# DAUGHTERBOARD.net
KiCad netlist of a schematic drawn in Altium Designer
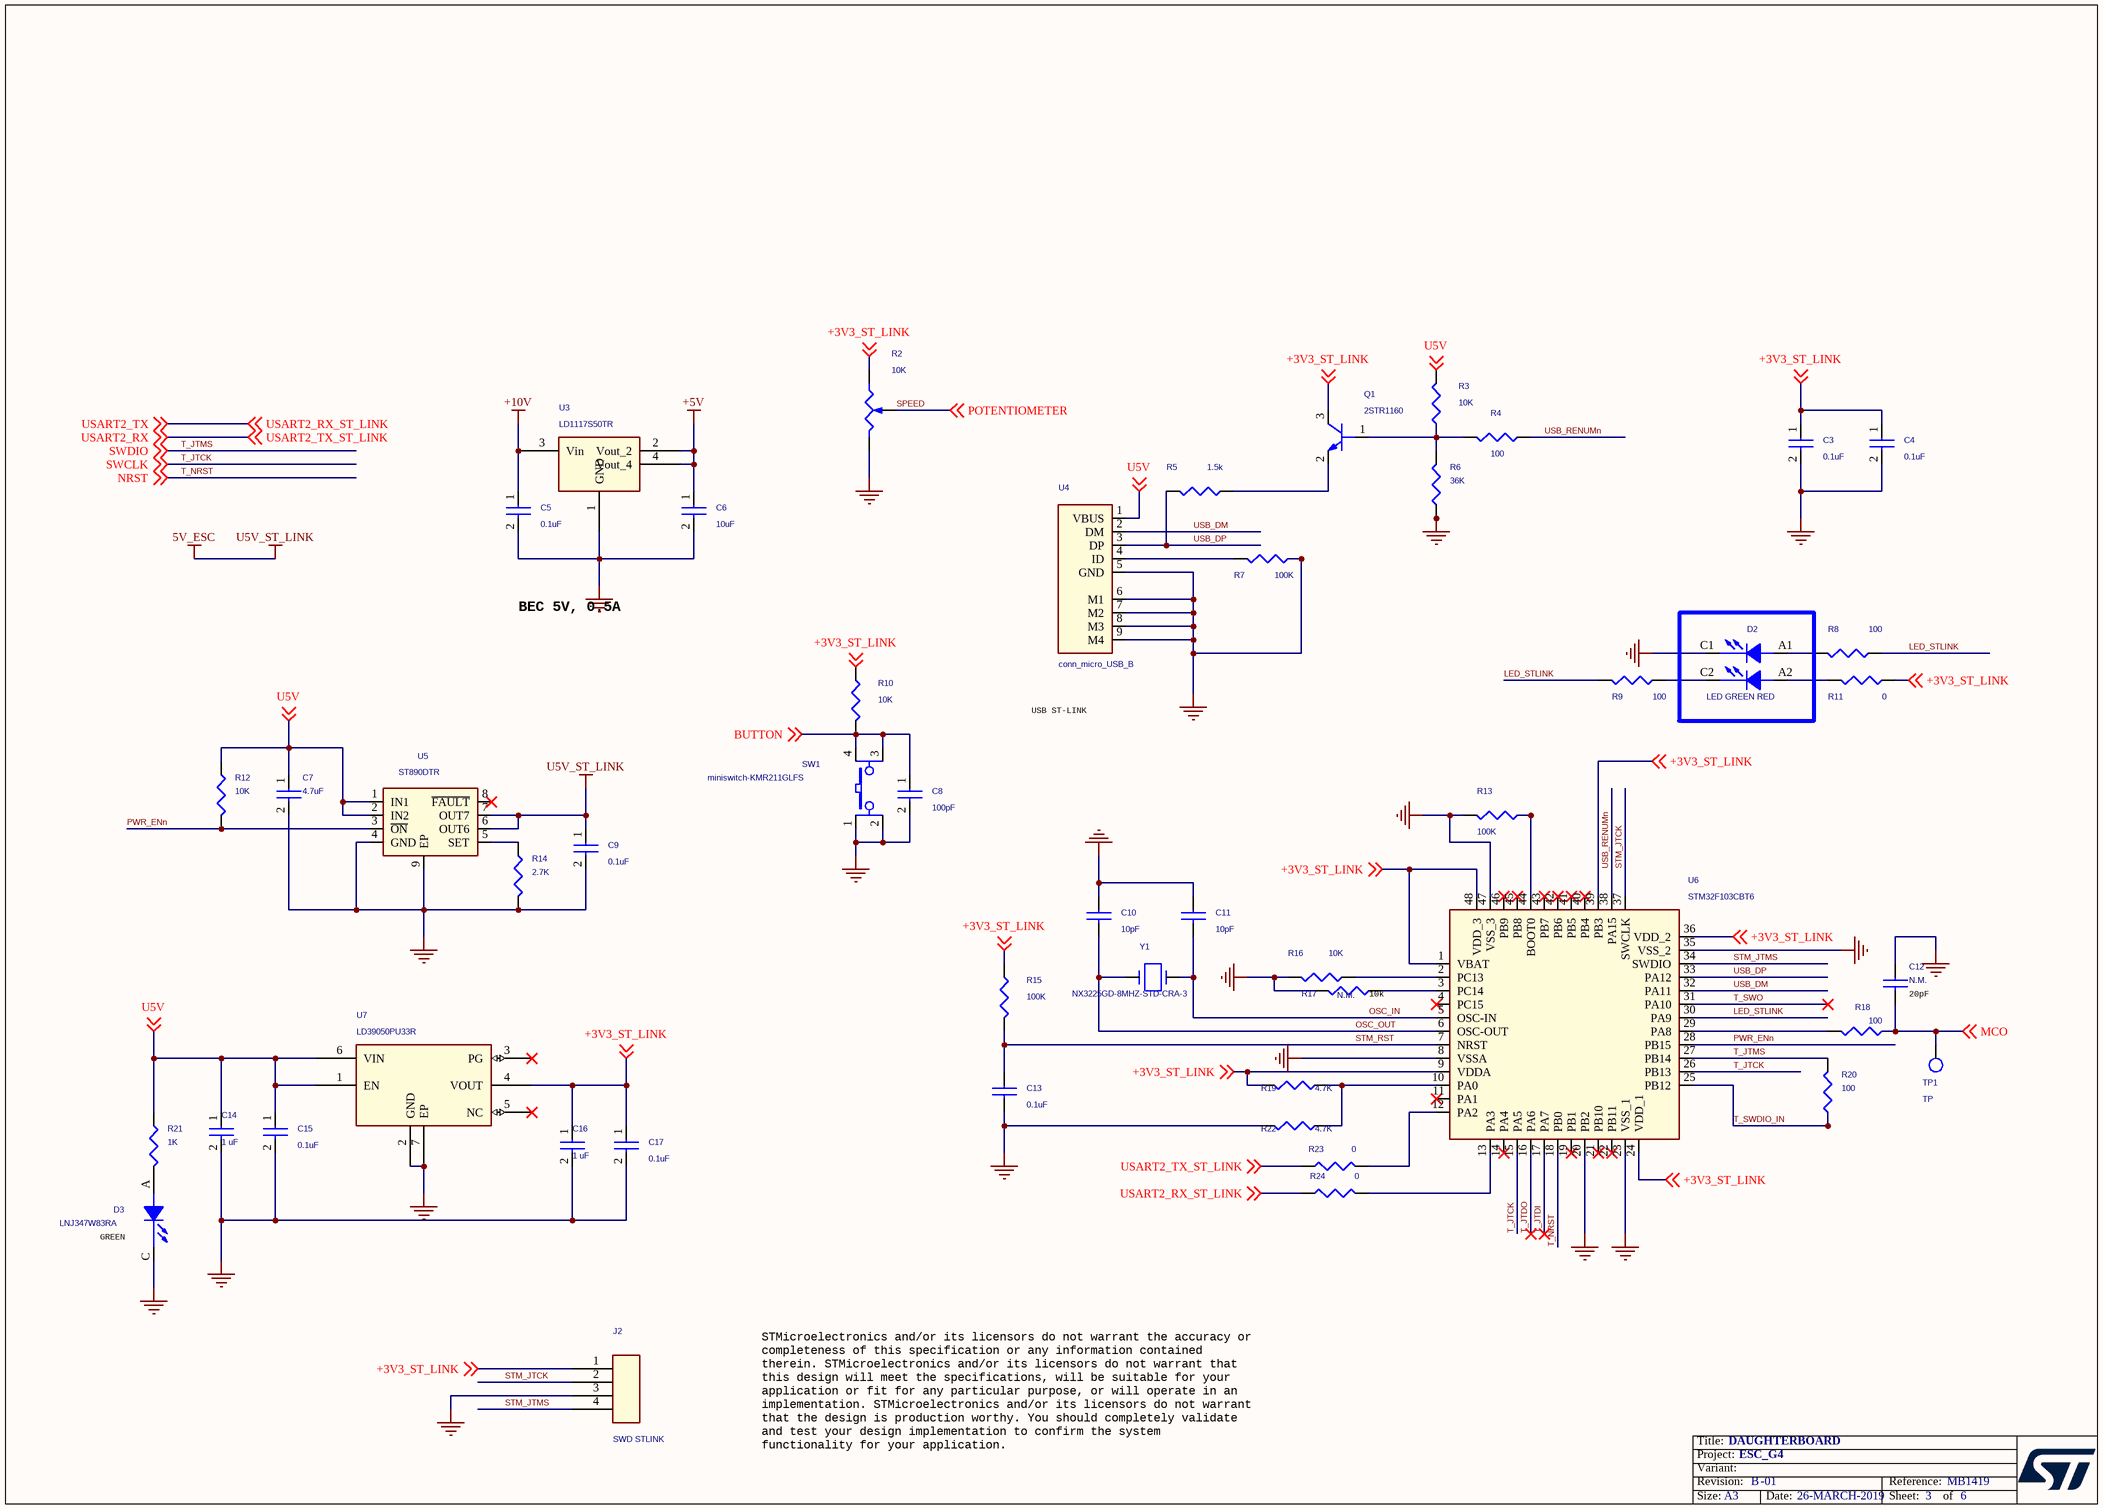
[diagram p0: DAUGHTERBOARD.SchDoc]

(export (version "E")
  (design (tool "Eeschema 10.0.6"))
  (components
    (comp (ref "C3")
      (value "0.1uF")
      (footprint "C_0402")
      (description "CAP CER 0.1UF 16V X7R 0402")
      (fields (field (name "MANUFACTURER") "Wurth Electronics Inc.") (field (name "TOLERANCE") "10%"))
      (libsource (lib "*") (part "CAP_Dup1"))
    )
    (comp (ref "C4")
      (value "0.1uF")
      (footprint "C_0402")
      (description "CAP CER 0.1UF 16V X7R 0402")
      (fields (field (name "MANUFACTURER") "Wurth Electronics Inc.") (field (name "TOLERANCE") "10%"))
      (libsource (lib "*") (part "CAP_Dup1"))
    )
    (comp (ref "C5")
      (value "0.1uF")
      (footprint "C_0402")
      (description "CAP CER 0.1UF 16V X7R 0402")
      (fields (field (name "MANUFACTURER") "Wurth Electronics Inc.") (field (name "TOLERANCE") "10%"))
      (libsource (lib "*") (part "CAP_Dup1"))
    )
    (comp (ref "C6")
      (value "10uF")
      (footprint "C_0805")
      (description "CAP CER 10UF 16V X5R 0805")
      (fields (field (name "MANUFACTURER") "Wurth Electronics Inc.") (field (name "TOLERANCE") "20%"))
      (libsource (lib "*") (part "CAP_Dup1"))
    )
    (comp (ref "C7")
      (value "4.7uF")
      (footprint "C_0805")
      (description "CAP CER 4.7UF 16V X5R 0805")
      (fields (field (name "PART_NUMBER") "TMP-410") (field (name "TOLERANCE") "20%"))
      (libsource (lib "*") (part "CAP_Dup1"))
    )
    (comp (ref "C8")
      (value "100pF")
      (footprint "C_0402")
      (description "CAP CER 100PF 10V C0G/NP0 0402")
      (fields (field (name "PART_NUMBER") "TMP-412") (field (name "TOLERANCE") "5%"))
      (libsource (lib "*") (part "CAP_Dup1"))
    )
    (comp (ref "C9")
      (value "0.1uF")
      (footprint "C_0402")
      (description "CAP CER 0.1UF 16V X7R 0402")
      (fields (field (name "MANUFACTURER") "Wurth Electronics Inc.") (field (name "TOLERANCE") "10%"))
      (libsource (lib "*") (part "CAP_Dup1"))
    )
    (comp (ref "C10")
      (value "10pF")
      (footprint "C_0402")
      (description "CAP CER 10PF 10V C0G/NP0 0402")
      (fields (field (name "PART_NUMBER") "TMP-395") (field (name "TOLERANCE") "5%"))
      (libsource (lib "*") (part "CAP_7"))
    )
    (comp (ref "C11")
      (value "10pF")
      (footprint "C_0402")
      (description "CAP CER 10PF 10V C0G/NP0 0402")
      (fields (field (name "PART_NUMBER") "TMP-395") (field (name "TOLERANCE") "5%"))
      (libsource (lib "*") (part "CAP_7"))
    )
    (comp (ref "C12")
      (value "N.M.")
      (footprint "C_0402")
      (description "CAP CER 0402-NOT MOUNTED")
      (fields (field (name "PART_NUMBER") "TMP-408"))
      (libsource (lib "*") (part "CAP_6"))
    )
    (comp (ref "C13")
      (value "0.1uF")
      (footprint "C_0402")
      (description "CAP CER 0.1UF 16V X7R 0402")
      (fields (field (name "PART_NUMBER") "CAP-00000053") (field (name "TOLERANCE") "10%"))
      (libsource (lib "*") (part "CAP_8"))
    )
    (comp (ref "C14")
      (value "1 uF")
      (footprint "C_0603")
      (description "CAP CER 1UF 16V X5R 0603")
      (fields (field (name "PART_NUMBER") "TMP-302") (field (name "TOLERANCE") "10%"))
      (libsource (lib "*") (part "CAP_Dup1"))
    )
    (comp (ref "C15")
      (value "0.1uF")
      (footprint "C_0603")
      (description "CAP CER 0.1UF 16V X7R 0603")
      (fields (field (name "MANUFACTURER") "Wurth Electronics Inc.") (field (name "TOLERANCE") "10%"))
      (libsource (lib "*") (part "CAP_Dup1"))
    )
    (comp (ref "C16")
      (value "1 uF")
      (footprint "C_0603")
      (description "CAP CER 1UF 16V X5R 0603")
      (fields (field (name "PART_NUMBER") "TMP-302") (field (name "TOLERANCE") "10%"))
      (libsource (lib "*") (part "CAP_Dup1"))
    )
    (comp (ref "C17")
      (value "0.1uF")
      (footprint "C_0402")
      (description "CAP CER 0.1UF 16V X7R 0402")
      (fields (field (name "PART_NUMBER") "CAP-00000053") (field (name "TOLERANCE") "10%"))
      (libsource (lib "*") (part "CAP_Dup1"))
    )
    (comp (ref "D2")
      (value "LED GREEN RED")
      (footprint "Led_bicolor_3528-PLCC-4")
      (description "LED GREEN/RED CLEAR 4PLCC SMD")
      (fields (field (name "PART_NUMBER") "TMP-705") (field (name "MANUFACTURER") "Wurth Electronics Inc."))
      (libsource (lib "*") (part "LED_BICOLOR"))
    )
    (comp (ref "D3")
      (value "LNJ347W83RA")
      (footprint "D_0402_Led_green")
      (description "LED GREEN 0402 SMD")
      (fields
        (field (name "MANUFACTURER") "Panasonic Electronic Components")
        (field (name "PART_NUMBER") "TMP-187")
      )
      (libsource (lib "*") (part "LED"))
    )
    (comp (ref "J2")
      (value "SWD STLINK")
      (footprint "strip4_100m_v")
      (description "SOLDER PADS")
      (libsource (lib "*") (part "CON4"))
    )
    (comp (ref "Q1")
      (value "2STR1160")
      (footprint "sot23-3p97_255x140l40x40n")
      (description "TRANS NPN 60V 1A SOT-23")
      (fields (field (name "PART_NUMBER") "TMP-433") (field (name "MANUFACTURER") "STMicroelectronics"))
      (libsource (lib "*") (part "BJT_NPN_BEC"))
    )
    (comp (ref "R2")
      (value "10K")
      (footprint "trimmer-3386P_T")
      (description "TRIMMER 10K OHM 0.5W PC PIN")
      (fields (field (name "PART_NUMBER") "TMP-491") (field (name "TOLERANCE") "10%"))
      (libsource (lib "*") (part "POT"))
    )
    (comp (ref "R3")
      (value "10K")
      (footprint "R_0402")
      (description "RES SMD 10K OHM 1% 1/16W 0402")
      (fields (field (name "MANUFACTURER") "Yageo") (field (name "TOLERANCE") "1%"))
      (libsource (lib "*") (part "RES"))
    )
    (comp (ref "R4")
      (value "100")
      (footprint "R_0402")
      (description "RES SMD 100 OHM 1% 1/16W 0402")
      (fields (field (name "PART_NUMBER") "TMP-406") (field (name "TOLERANCE") "1%"))
      (libsource (lib "*") (part "RES"))
    )
    (comp (ref "R5")
      (value "1.5k")
      (footprint "R_0402")
      (description "RES SMD 1.5K OHM 1% 1/16W 0402")
      (fields (field (name "PART_NUMBER") "TMP-393") (field (name "TOLERANCE") "1%"))
      (libsource (lib "*") (part "RES"))
    )
    (comp (ref "R6")
      (value "36K")
      (footprint "R_0402")
      (description "RES SMD 36K OHM 1% 1/16W 0402")
      (fields (field (name "MANUFACTURER") "Yageo") (field (name "TOLERANCE") "1%"))
      (libsource (lib "*") (part "RES"))
    )
    (comp (ref "R7")
      (value "100K")
      (footprint "R_0402")
      (description "RES SMD 100K OHM 1% 1/16W 0402")
      (fields (field (name "MANUFACTURER") "TE Connectivity Passive Product") (field (name "TOLERANCE") "1%"))
      (libsource (lib "*") (part "RES"))
    )
    (comp (ref "R8")
      (value "100")
      (footprint "R_0402")
      (description "RES SMD 100 OHM 1% 1/16W 0402")
      (fields (field (name "PART_NUMBER") "TMP-406") (field (name "TOLERANCE") "1%"))
      (libsource (lib "*") (part "RES"))
    )
    (comp (ref "R9")
      (value "100")
      (footprint "R_0402")
      (description "RES SMD 100 OHM 1% 1/16W 0402")
      (fields (field (name "MANUFACTURER") "TE Connectivity Passive Product") (field (name "TOLERANCE") "1%"))
      (libsource (lib "*") (part "RES"))
    )
    (comp (ref "R10")
      (value "10K")
      (footprint "R_0402")
      (description "RES SMD 10K OHM 1% 1/16W 0402")
      (fields (field (name "PART_NUMBER") "TMP-396") (field (name "TOLERANCE") "1%"))
      (libsource (lib "*") (part "RES"))
    )
    (comp (ref "R11")
      (value "0")
      (footprint "R_0402")
      (description "RES SMD 0 OHM JUMPER 1/16W 0402")
      (fields (field (name "MANUFACTURER") "Vishay Dale") (field (name "TOLERANCE") "Jumper"))
      (libsource (lib "*") (part "RES"))
    )
    (comp (ref "R12")
      (value "10K")
      (footprint "R_0402")
      (description "RES SMD 10K OHM 1% 1/16W 0402")
      (fields (field (name "MANUFACTURER") "Yageo") (field (name "TOLERANCE") "1%"))
      (libsource (lib "*") (part "RES"))
    )
    (comp (ref "R13")
      (value "100K")
      (footprint "R_0402")
      (description "RES SMD 100K OHM 1% 1/16W 0402")
      (fields (field (name "MANUFACTURER") "TE Connectivity Passive Product") (field (name "TOLERANCE") "1%"))
      (libsource (lib "*") (part "RES"))
    )
    (comp (ref "R14")
      (value "2.7K")
      (footprint "R_0402")
      (description "RES SMD 2.7K OHM 1% 1/16W 0402")
      (fields (field (name "PART_NUMBER") "TMP-411") (field (name "TOLERANCE") "1%"))
      (libsource (lib "*") (part "RES"))
    )
    (comp (ref "R15")
      (value "100K")
      (footprint "R_0402")
      (description "RES SMD 100K OHM 1% 1/16W 0402")
      (fields (field (name "PART_NUMBER") "TMP-405") (field (name "TOLERANCE") "1%"))
      (libsource (lib "*") (part "RES"))
    )
    (comp (ref "R16")
      (value "10K")
      (footprint "R_0402")
      (description "RES SMD 10K OHM 1% 1/16W 0402")
      (fields (field (name "PART_NUMBER") "TMP-396") (field (name "TOLERANCE") "1%"))
      (libsource (lib "*") (part "RES"))
    )
    (comp (ref "R17")
      (value "N.M.")
      (footprint "R_0402")
      (description "RES SMD 0402 - NOT MOUNTED")
      (fields (field (name "PART_NUMBER") "TMP-404"))
      (libsource (lib "*") (part "RES"))
    )
    (comp (ref "R18")
      (value "100")
      (footprint "R_0402")
      (description "RES SMD 100 OHM 1% 1/16W 0402")
      (fields (field (name "MANUFACTURER") "TE Connectivity Passive Product") (field (name "TOLERANCE") "1%"))
      (libsource (lib "*") (part "RES"))
    )
    (comp (ref "R19")
      (value "4.7K")
      (footprint "R_0402")
      (description "RES SMD 4.7K OHM 1% 1/16W 0402")
      (fields (field (name "PART_NUMBER") "TMP-403") (field (name "TOLERANCE") "1%"))
      (libsource (lib "*") (part "RES"))
    )
    (comp (ref "R20")
      (value "100")
      (footprint "R_0402")
      (description "RES SMD 100 OHM 1% 1/16W 0402")
      (fields (field (name "PART_NUMBER") "TMP-406") (field (name "TOLERANCE") "1%"))
      (libsource (lib "*") (part "RES"))
    )
    (comp (ref "R21")
      (value "1K")
      (footprint "R_0402")
      (description "RES SMD 1K OHM 1% 1/16W 0402")
      (fields (field (name "PART_NUMBER") "TMP-352") (field (name "TOLERANCE") "1%"))
      (libsource (lib "*") (part "RES"))
    )
    (comp (ref "R22")
      (value "4.7K")
      (footprint "R_0402")
      (description "RES SMD 4.7K OHM 1% 1/16W 0402")
      (fields (field (name "PART_NUMBER") "TMP-403") (field (name "TOLERANCE") "1%"))
      (libsource (lib "*") (part "RES"))
    )
    (comp (ref "R23")
      (value "0")
      (footprint "JUMPER_0603_DROP")
      (description "RES SMD 0 OHM JUMPER 1/10W 0603")
      (fields
        (field (name "MANUFACTURER") "Panasonic Electronic Components")
        (field (name "TOLERANCE") "Jumper")
      )
      (libsource (lib "*") (part "RES"))
    )
    (comp (ref "R24")
      (value "0")
      (footprint "JUMPER_0603_DROP")
      (description "RES SMD 0 OHM JUMPER 1/10W 0603")
      (fields (field (name "PART_NUMBER") "RES-00000056") (field (name "TOLERANCE") "Jumper"))
      (libsource (lib "*") (part "RES"))
    )
    (comp (ref "SW1")
      (value "miniswitch-KMR211GLFS")
      (footprint "switch_SMT_4_2x2_8mm")
      (description "SWITCH TACTILE SPST-NO 0.05A 32V")
      (fields (field (name "MANUFACTURER") "C&K") (field (name "PART_NUMBER") "TMP-285"))
      (libsource (lib "*") (part "PUSHBUTTON-SPST-2"))
    )
    (comp (ref "TP1")
      (value "TP")
      (footprint "test_point_100_smd")
      (description "TEST POINT 1MM  SMD PADSTASCK")
      (fields (field (name "PART_NUMBER") "TMP-386"))
      (libsource (lib "*") (part "TESTPOINT"))
    )
    (comp (ref "U3")
      (value "LD1117S50TR")
      (footprint "sot223-4p230_700x190l65x72")
      (description "IC REG LINEAR 5V 800MA SOT223")
      (fields (field (name "MANUFACTURER") "STMicroelectronics") (field (name "PART_NUMBER") "TMP-381"))
      (libsource (lib "*") (part "LD1117SxxxTR_0"))
    )
    (comp (ref "U4")
      (value "conn_micro_USB_B")
      (footprint "conn_micro_USB_B_SMD")
      (description "CONN RCPT 5POS MICRO USB R/A")
      (fields (field (name "MANUFACTURER") "Molex, LLC") (field (name "PART_NUMBER") "TMP-434"))
      (libsource (lib "*") (part "USB_MICRO"))
    )
    (comp (ref "U5")
      (value "ST890DTR")
      (footprint "son9p65_300x300x90l30x30t240-1")
      (description "IC PWR SWITCH 1.2A HISIDE 8-DFN")
      (fields (field (name "MANUFACTURER") "STMicroelectronics") (field (name "PART_NUMBER") "TMP-432"))
      (libsource (lib "*") (part "ST890DTR"))
    )
    (comp (ref "U6")
      (value "STM32F103CBT6")
      (footprint "qfp48p50_900x900x160l60x22n")
      (description "IC MCU 32BIT 128KB FLASH 48LQFP")
      (fields (field (name "PART_NUMBER") "TMP-399") (field (name "MANUFACTURER") "STMicroelectronics"))
      (libsource (lib "*") (part "STM32F103CBT6"))
    )
    (comp (ref "U7")
      (value "LD39050PU33R")
      (footprint "son7p95_300x300x100l40x34t23-1")
      (description "IC REG LINEAR 3.3V 500MA 6DFN")
      (fields (field (name "PART_NUMBER") "TMP-358") (field (name "MANUFACTURER") "STMicroelectronics"))
      (libsource (lib "*") (part "LD39050PU33R"))
    )
    (comp (ref "Y1")
      (value "NX3225GD-8MHZ-STD-CRA-3")
      (footprint "xtaldfn2_320x250x100l130x230")
      (description "CRYSTAL 8.0000MHZ 8PF SMD")
      (fields (field (name "MANUFACTURER") "NDK America, Inc.") (field (name "PART_NUMBER") "TMP-435"))
      (libsource (lib "*") (part "crystal"))
    )
  )
  (nets
    (net (code "1") (name "+3V3_ST_LINK") (class "Default")
      (node (ref "C16") (pin "1") (pinfunction "1_1") (pintype "passive"))
      (node (ref "C17") (pin "1") (pinfunction "1_1") (pintype "passive"))
      (node (ref "C3") (pin "1") (pinfunction "1_1") (pintype "passive"))
      (node (ref "C4") (pin "1") (pinfunction "1_1") (pintype "passive"))
      (node (ref "J2") (pin "1") (pinfunction "1_1") (pintype "passive"))
      (node (ref "Q1") (pin "3") (pinfunction "C_3") (pintype "passive"))
      (node (ref "R10") (pin "1") (pinfunction "1_1") (pintype "passive"))
      (node (ref "R11") (pin "1") (pinfunction "1_1") (pintype "passive"))
      (node (ref "R15") (pin "1") (pinfunction "1_1") (pintype "passive"))
      (node (ref "R19") (pin "2") (pinfunction "2_2") (pintype "passive"))
      (node (ref "R2") (pin "3") (pinfunction "B_3") (pintype "passive"))
      (node (ref "U6") (pin "1") (pinfunction "VBAT_1") (pintype "passive"))
      (node (ref "U6") (pin "24") (pinfunction "VDD_1_24") (pintype "passive"))
      (node (ref "U6") (pin "36") (pinfunction "VDD_2_36") (pintype "passive"))
      (node (ref "U6") (pin "39") (pinfunction "PB3_39") (pintype "passive"))
      (node (ref "U6") (pin "48") (pinfunction "VDD_3_48") (pintype "passive"))
      (node (ref "U6") (pin "9") (pinfunction "VDDA_9") (pintype "passive"))
      (node (ref "U7") (pin "4") (pinfunction "VOUT_4") (pintype "power_in"))
    )
    (net (code "2") (name "+5V") (class "Default")
      (node (ref "C6") (pin "1") (pinfunction "1_1") (pintype "passive"))
      (node (ref "U3") (pin "2") (pinfunction "Vout_2_2") (pintype "passive"))
      (node (ref "U3") (pin "4") (pinfunction "Vout_4_4") (pintype "passive"))
    )
    (net (code "3") (name "+10V") (class "Default")
      (node (ref "C5") (pin "1") (pinfunction "1_1") (pintype "passive"))
      (node (ref "U3") (pin "3") (pinfunction "Vin_3") (pintype "passive"))
    )
    (net (code "4") (name "/LED_STLINK") (class "Default")
      (node (ref "R8") (pin "1") (pinfunction "1_1") (pintype "passive"))
      (node (ref "R9") (pin "2") (pinfunction "2_2") (pintype "passive"))
      (node (ref "U6") (pin "30") (pinfunction "PA9_30") (pintype "passive"))
    )
    (net (code "5") (name "/OSC_IN") (class "Default")
      (node (ref "C11") (pin "2") (pinfunction "2_2") (pintype "passive"))
      (node (ref "U6") (pin "5") (pinfunction "OSC-IN_5") (pintype "passive"))
      (node (ref "Y1") (pin "1") (pinfunction "1_1") (pintype "passive"))
    )
    (net (code "6") (name "/OSC_OUT") (class "Default")
      (node (ref "C10") (pin "2") (pinfunction "2_2") (pintype "passive"))
      (node (ref "U6") (pin "6") (pinfunction "OSC-OUT_6") (pintype "passive"))
      (node (ref "Y1") (pin "2") (pinfunction "2_2") (pintype "passive"))
    )
    (net (code "7") (name "/PWR_ENn") (class "Default")
      (node (ref "R12") (pin "2") (pinfunction "2_2") (pintype "passive"))
      (node (ref "U5") (pin "3") (pinfunction "~{ON}_3") (pintype "passive"))
      (node (ref "U6") (pin "28") (pinfunction "PB15_28") (pintype "passive"))
    )
    (net (code "8") (name "/STM_JTCK") (class "Default")
      (node (ref "J2") (pin "2") (pinfunction "2_2") (pintype "passive"))
      (node (ref "U6") (pin "37") (pinfunction "SWCLK_37") (pintype "passive"))
    )
    (net (code "9") (name "/STM_JTMS") (class "Default")
      (node (ref "J2") (pin "4") (pinfunction "4_4") (pintype "passive"))
      (node (ref "U6") (pin "34") (pinfunction "SWDIO_34") (pintype "passive"))
    )
    (net (code "10") (name "/STM_RST") (class "Default")
      (node (ref "C13") (pin "1") (pinfunction "1_1") (pintype "passive"))
      (node (ref "R15") (pin "2") (pinfunction "2_2") (pintype "passive"))
      (node (ref "U6") (pin "7") (pinfunction "NRST_7") (pintype "passive"))
    )
    (net (code "11") (name "/T_JTDI") (class "Default")
      (node (ref "U6") (pin "17") (pinfunction "PA7_17") (pintype "passive+no_connect"))
    )
    (net (code "12") (name "/T_JTDO") (class "Default")
      (node (ref "U6") (pin "16") (pinfunction "PA6_16") (pintype "passive+no_connect"))
    )
    (net (code "13") (name "/T_SWDIO_IN") (class "Default")
      (node (ref "R20") (pin "1") (pinfunction "1_1") (pintype "passive"))
      (node (ref "U6") (pin "25") (pinfunction "PB12_25") (pintype "passive"))
    )
    (net (code "14") (name "/T_SWO") (class "Default")
      (node (ref "U6") (pin "31") (pinfunction "PA10_31") (pintype "passive+no_connect"))
    )
    (net (code "15") (name "/USB_DM") (class "Default")
      (node (ref "U4") (pin "2") (pinfunction "DM_2") (pintype "passive"))
      (node (ref "U6") (pin "32") (pinfunction "PA11_32") (pintype "passive"))
    )
    (net (code "16") (name "/USB_DP") (class "Default")
      (node (ref "R5") (pin "2") (pinfunction "2_2") (pintype "passive"))
      (node (ref "U4") (pin "3") (pinfunction "DP_3") (pintype "passive"))
      (node (ref "U6") (pin "33") (pinfunction "PA12_33") (pintype "passive"))
    )
    (net (code "17") (name "/USB_RENUMn") (class "Default")
      (node (ref "R4") (pin "1") (pinfunction "1_1") (pintype "passive"))
      (node (ref "U6") (pin "38") (pinfunction "PA15_38") (pintype "passive"))
    )
    (net (code "18") (name "5V_ESC") (class "Default")
      (node (ref "C9") (pin "1") (pinfunction "1_1") (pintype "passive"))
      (node (ref "U5") (pin "6") (pinfunction "OUT6_6") (pintype "passive"))
      (node (ref "U5") (pin "7") (pinfunction "OUT7_7") (pintype "passive"))
    )
    (net (code "19") (name "BUTTON") (class "Default")
      (node (ref "C8") (pin "1") (pinfunction "1_1") (pintype "passive"))
      (node (ref "R10") (pin "2") (pinfunction "2_2") (pintype "passive"))
      (node (ref "SW1") (pin "3") (pinfunction "3_3") (pintype "passive"))
      (node (ref "SW1") (pin "4") (pinfunction "4_4") (pintype "passive"))
    )
    (net (code "20") (name "GND") (class "Default")
      (node (ref "C10") (pin "1") (pinfunction "1_1") (pintype "passive"))
      (node (ref "C11") (pin "1") (pinfunction "1_1") (pintype "passive"))
      (node (ref "C12") (pin "1") (pinfunction "1_1") (pintype "passive"))
      (node (ref "C13") (pin "2") (pinfunction "2_2") (pintype "passive"))
      (node (ref "C14") (pin "2") (pinfunction "2_2") (pintype "passive"))
      (node (ref "C15") (pin "2") (pinfunction "2_2") (pintype "passive"))
      (node (ref "C16") (pin "2") (pinfunction "2_2") (pintype "passive"))
      (node (ref "C17") (pin "2") (pinfunction "2_2") (pintype "passive"))
      (node (ref "C3") (pin "2") (pinfunction "2_2") (pintype "passive"))
      (node (ref "C4") (pin "2") (pinfunction "2_2") (pintype "passive"))
      (node (ref "C5") (pin "2") (pinfunction "2_2") (pintype "passive"))
      (node (ref "C6") (pin "2") (pinfunction "2_2") (pintype "passive"))
      (node (ref "C7") (pin "2") (pinfunction "2_2") (pintype "passive"))
      (node (ref "C8") (pin "2") (pinfunction "2_2") (pintype "passive"))
      (node (ref "C9") (pin "2") (pinfunction "2_2") (pintype "passive"))
      (node (ref "D2") (pin "C1") (pinfunction "CATHODE1_C1") (pintype "passive"))
      (node (ref "D3") (pin "C") (pinfunction "CATHODE_C") (pintype "passive"))
      (node (ref "J2") (pin "3") (pinfunction "3_3") (pintype "passive"))
      (node (ref "R13") (pin "2") (pinfunction "2_2") (pintype "passive"))
      (node (ref "R14") (pin "2") (pinfunction "2_2") (pintype "passive"))
      (node (ref "R16") (pin "2") (pinfunction "2_2") (pintype "passive"))
      (node (ref "R17") (pin "2") (pinfunction "2_2") (pintype "passive"))
      (node (ref "R2") (pin "1") (pinfunction "A_1") (pintype "passive"))
      (node (ref "R22") (pin "2") (pinfunction "2_2") (pintype "passive"))
      (node (ref "R6") (pin "1") (pinfunction "1_1") (pintype "passive"))
      (node (ref "R7") (pin "1") (pinfunction "1_1") (pintype "passive"))
      (node (ref "SW1") (pin "1") (pinfunction "1_1") (pintype "passive"))
      (node (ref "SW1") (pin "2") (pinfunction "2_2") (pintype "passive"))
      (node (ref "U3") (pin "1") (pinfunction "GND_1") (pintype "power_in"))
      (node (ref "U4") (pin "5") (pinfunction "GND_5") (pintype "passive"))
      (node (ref "U4") (pin "6") (pinfunction "M1_6") (pintype "passive"))
      (node (ref "U4") (pin "7") (pinfunction "M2_7") (pintype "passive"))
      (node (ref "U4") (pin "8") (pinfunction "M3_8") (pintype "passive"))
      (node (ref "U4") (pin "9") (pinfunction "M4_9") (pintype "passive"))
      (node (ref "U5") (pin "4") (pinfunction "GND_4") (pintype "passive"))
      (node (ref "U5") (pin "9") (pinfunction "EP_9") (pintype "passive"))
      (node (ref "U6") (pin "20") (pinfunction "PB2_20") (pintype "passive"))
      (node (ref "U6") (pin "23") (pinfunction "VSS_1_23") (pintype "passive"))
      (node (ref "U6") (pin "35") (pinfunction "VSS_2_35") (pintype "passive"))
      (node (ref "U6") (pin "47") (pinfunction "VSS_3_47") (pintype "passive"))
      (node (ref "U6") (pin "8") (pinfunction "VSSA_8") (pintype "passive"))
      (node (ref "U7") (pin "2") (pinfunction "GND_2") (pintype "power_in"))
      (node (ref "U7") (pin "7") (pinfunction "EP_7") (pintype "power_in"))
    )
    (net (code "21") (name "MCO") (class "Default")
      (node (ref "C12") (pin "2") (pinfunction "2_2") (pintype "passive"))
      (node (ref "R18") (pin "1") (pinfunction "1_1") (pintype "passive"))
      (node (ref "TP1") (pin "1") (pinfunction "1_1") (pintype "passive"))
    )
    (net (code "22") (name "NRST") (class "Default")
      (node (ref "U6") (pin "18") (pinfunction "PB0_18") (pintype "passive"))
    )
    (net (code "23") (name "Net-(D2-ANODE1)") (class "Default")
      (node (ref "D2") (pin "A1") (pinfunction "ANODE1_A1") (pintype "passive"))
      (node (ref "R8") (pin "2") (pinfunction "2_2") (pintype "passive"))
    )
    (net (code "24") (name "Net-(D2-ANODE2)") (class "Default")
      (node (ref "D2") (pin "A2") (pinfunction "ANODE2_A2") (pintype "passive"))
      (node (ref "R11") (pin "2") (pinfunction "2_2") (pintype "passive"))
    )
    (net (code "25") (name "Net-(D2-CATHODE2)") (class "Default")
      (node (ref "D2") (pin "C2") (pinfunction "CATHODE2_C2") (pintype "passive"))
      (node (ref "R9") (pin "1") (pinfunction "1_1") (pintype "passive"))
    )
    (net (code "26") (name "Net-(D3-ANODE)") (class "Default")
      (node (ref "D3") (pin "A") (pinfunction "ANODE_A") (pintype "passive"))
      (node (ref "R21") (pin "2") (pinfunction "2_2") (pintype "passive"))
    )
    (net (code "27") (name "Net-(Q1-B)") (class "Default")
      (node (ref "Q1") (pin "1") (pinfunction "B_1") (pintype "passive"))
      (node (ref "R3") (pin "1") (pinfunction "1_1") (pintype "passive"))
      (node (ref "R4") (pin "2") (pinfunction "2_2") (pintype "passive"))
      (node (ref "R6") (pin "2") (pinfunction "2_2") (pintype "passive"))
    )
    (net (code "28") (name "Net-(Q1-E)") (class "Default")
      (node (ref "Q1") (pin "2") (pinfunction "E_2") (pintype "passive"))
      (node (ref "R5") (pin "1") (pinfunction "1_1") (pintype "passive"))
    )
    (net (code "29") (name "Net-(U4-ID)") (class "Default")
      (node (ref "R7") (pin "2") (pinfunction "2_2") (pintype "passive"))
      (node (ref "U4") (pin "4") (pinfunction "ID_4") (pintype "passive"))
    )
    (net (code "30") (name "Net-(U5-SET)") (class "Default")
      (node (ref "R14") (pin "1") (pinfunction "1_1") (pintype "passive"))
      (node (ref "U5") (pin "5") (pinfunction "SET_5") (pintype "passive"))
    )
    (net (code "31") (name "Net-(U6-BOOT0)") (class "Default")
      (node (ref "R13") (pin "1") (pinfunction "1_1") (pintype "passive"))
      (node (ref "U6") (pin "44") (pinfunction "BOOT0_44") (pintype "passive"))
    )
    (net (code "32") (name "Net-(U6-PA0)") (class "Default")
      (node (ref "R19") (pin "1") (pinfunction "1_1") (pintype "passive"))
      (node (ref "R22") (pin "1") (pinfunction "1_1") (pintype "passive"))
      (node (ref "U6") (pin "10") (pinfunction "PA0_10") (pintype "passive"))
    )
    (net (code "33") (name "Net-(U6-PA2)") (class "Default")
      (node (ref "R23") (pin "2") (pinfunction "2_2") (pintype "passive"))
      (node (ref "U6") (pin "12") (pinfunction "PA2_12") (pintype "passive"))
    )
    (net (code "34") (name "Net-(U6-PA3)") (class "Default")
      (node (ref "R24") (pin "2") (pinfunction "2_2") (pintype "passive"))
      (node (ref "U6") (pin "13") (pinfunction "PA3_13") (pintype "passive"))
    )
    (net (code "35") (name "Net-(U6-PA8)") (class "Default")
      (node (ref "R18") (pin "2") (pinfunction "2_2") (pintype "passive"))
      (node (ref "U6") (pin "29") (pinfunction "PA8_29") (pintype "passive"))
    )
    (net (code "36") (name "Net-(U6-PC13)") (class "Default")
      (node (ref "R16") (pin "1") (pinfunction "1_1") (pintype "passive"))
      (node (ref "U6") (pin "2") (pinfunction "PC13_2") (pintype "passive"))
    )
    (net (code "37") (name "Net-(U6-PC14)") (class "Default")
      (node (ref "R17") (pin "1") (pinfunction "1_1") (pintype "passive"))
      (node (ref "U6") (pin "3") (pinfunction "PC14_3") (pintype "passive"))
    )
    (net (code "38") (name "POTENTIOMETER") (class "Default")
      (node (ref "R2") (pin "2") (pinfunction "WIPER_2") (pintype "passive"))
    )
    (net (code "39") (name "SWCLK") (class "Default")
      (node (ref "U6") (pin "15") (pinfunction "PA5_15") (pintype "passive"))
      (node (ref "U6") (pin "26") (pinfunction "PB13_26") (pintype "passive"))
    )
    (net (code "40") (name "SWDIO") (class "Default")
      (node (ref "R20") (pin "2") (pinfunction "2_2") (pintype "passive"))
      (node (ref "U6") (pin "27") (pinfunction "PB14_27") (pintype "passive"))
    )
    (net (code "41") (name "U5V") (class "Default")
      (node (ref "C14") (pin "1") (pinfunction "1_1") (pintype "passive"))
      (node (ref "C15") (pin "1") (pinfunction "1_1") (pintype "passive"))
      (node (ref "C7") (pin "1") (pinfunction "1_1") (pintype "passive"))
      (node (ref "R12") (pin "1") (pinfunction "1_1") (pintype "passive"))
      (node (ref "R21") (pin "1") (pinfunction "1_1") (pintype "passive"))
      (node (ref "R3") (pin "2") (pinfunction "2_2") (pintype "passive"))
      (node (ref "U4") (pin "1") (pinfunction "VBUS_1") (pintype "passive"))
      (node (ref "U5") (pin "1") (pinfunction "IN1_1") (pintype "passive"))
      (node (ref "U5") (pin "2") (pinfunction "IN2_2") (pintype "passive"))
      (node (ref "U7") (pin "1") (pinfunction "EN_1") (pintype "power_in"))
      (node (ref "U7") (pin "6") (pinfunction "VIN_6") (pintype "power_in"))
    )
    (net (code "42") (name "USART2_RX") (class "Default")
      (node (ref "R23") (pin "1") (pinfunction "1_1") (pintype "passive"))
    )
    (net (code "43") (name "USART2_RX_ST_LINK") (class "Default")
      (node (ref "R24") (pin "1") (pinfunction "1_1") (pintype "passive"))
    )
    (net (code "44") (name "unconnected-(U5-~{FAULT}-Pad8)") (class "Default")
      (node (ref "U5") (pin "8") (pinfunction "~{FAULT}_8") (pintype "passive+no_connect"))
    )
    (net (code "45") (name "unconnected-(U6-PA1-Pad11)") (class "Default")
      (node (ref "U6") (pin "11") (pinfunction "PA1_11") (pintype "passive+no_connect"))
    )
    (net (code "46") (name "unconnected-(U6-PA4-Pad14)") (class "Default")
      (node (ref "U6") (pin "14") (pinfunction "PA4_14") (pintype "passive+no_connect"))
    )
    (net (code "47") (name "unconnected-(U6-PB1-Pad19)") (class "Default")
      (node (ref "U6") (pin "19") (pinfunction "PB1_19") (pintype "passive+no_connect"))
    )
    (net (code "48") (name "unconnected-(U6-PB4-Pad40)") (class "Default")
      (node (ref "U6") (pin "40") (pinfunction "PB4_40") (pintype "passive+no_connect"))
    )
    (net (code "49") (name "unconnected-(U6-PB5-Pad41)") (class "Default")
      (node (ref "U6") (pin "41") (pinfunction "PB5_41") (pintype "passive+no_connect"))
    )
    (net (code "50") (name "unconnected-(U6-PB6-Pad42)") (class "Default")
      (node (ref "U6") (pin "42") (pinfunction "PB6_42") (pintype "passive+no_connect"))
    )
    (net (code "51") (name "unconnected-(U6-PB7-Pad43)") (class "Default")
      (node (ref "U6") (pin "43") (pinfunction "PB7_43") (pintype "passive+no_connect"))
    )
    (net (code "52") (name "unconnected-(U6-PB8-Pad45)") (class "Default")
      (node (ref "U6") (pin "45") (pinfunction "PB8_45") (pintype "passive+no_connect"))
    )
    (net (code "53") (name "unconnected-(U6-PB9-Pad46)") (class "Default")
      (node (ref "U6") (pin "46") (pinfunction "PB9_46") (pintype "passive+no_connect"))
    )
    (net (code "54") (name "unconnected-(U6-PB10-Pad21)") (class "Default")
      (node (ref "U6") (pin "21") (pinfunction "PB10_21") (pintype "passive+no_connect"))
    )
    (net (code "55") (name "unconnected-(U6-PB11-Pad22)") (class "Default")
      (node (ref "U6") (pin "22") (pinfunction "PB11_22") (pintype "passive+no_connect"))
    )
    (net (code "56") (name "unconnected-(U6-PC15-Pad4)") (class "Default")
      (node (ref "U6") (pin "4") (pinfunction "PC15_4") (pintype "passive+no_connect"))
    )
    (net (code "57") (name "unconnected-(U7-NC-Pad5)") (class "Default")
      (node (ref "U7") (pin "5") (pinfunction "NC_5") (pintype "bidirectional+no_connect"))
    )
    (net (code "58") (name "unconnected-(U7-PG-Pad3)") (class "Default")
      (node (ref "U7") (pin "3") (pinfunction "PG_3") (pintype "bidirectional+no_connect"))
    )
  )
)
